# Schematic_v1_1_1.net
KiCad netlist of a schematic drawn in EasyEDA
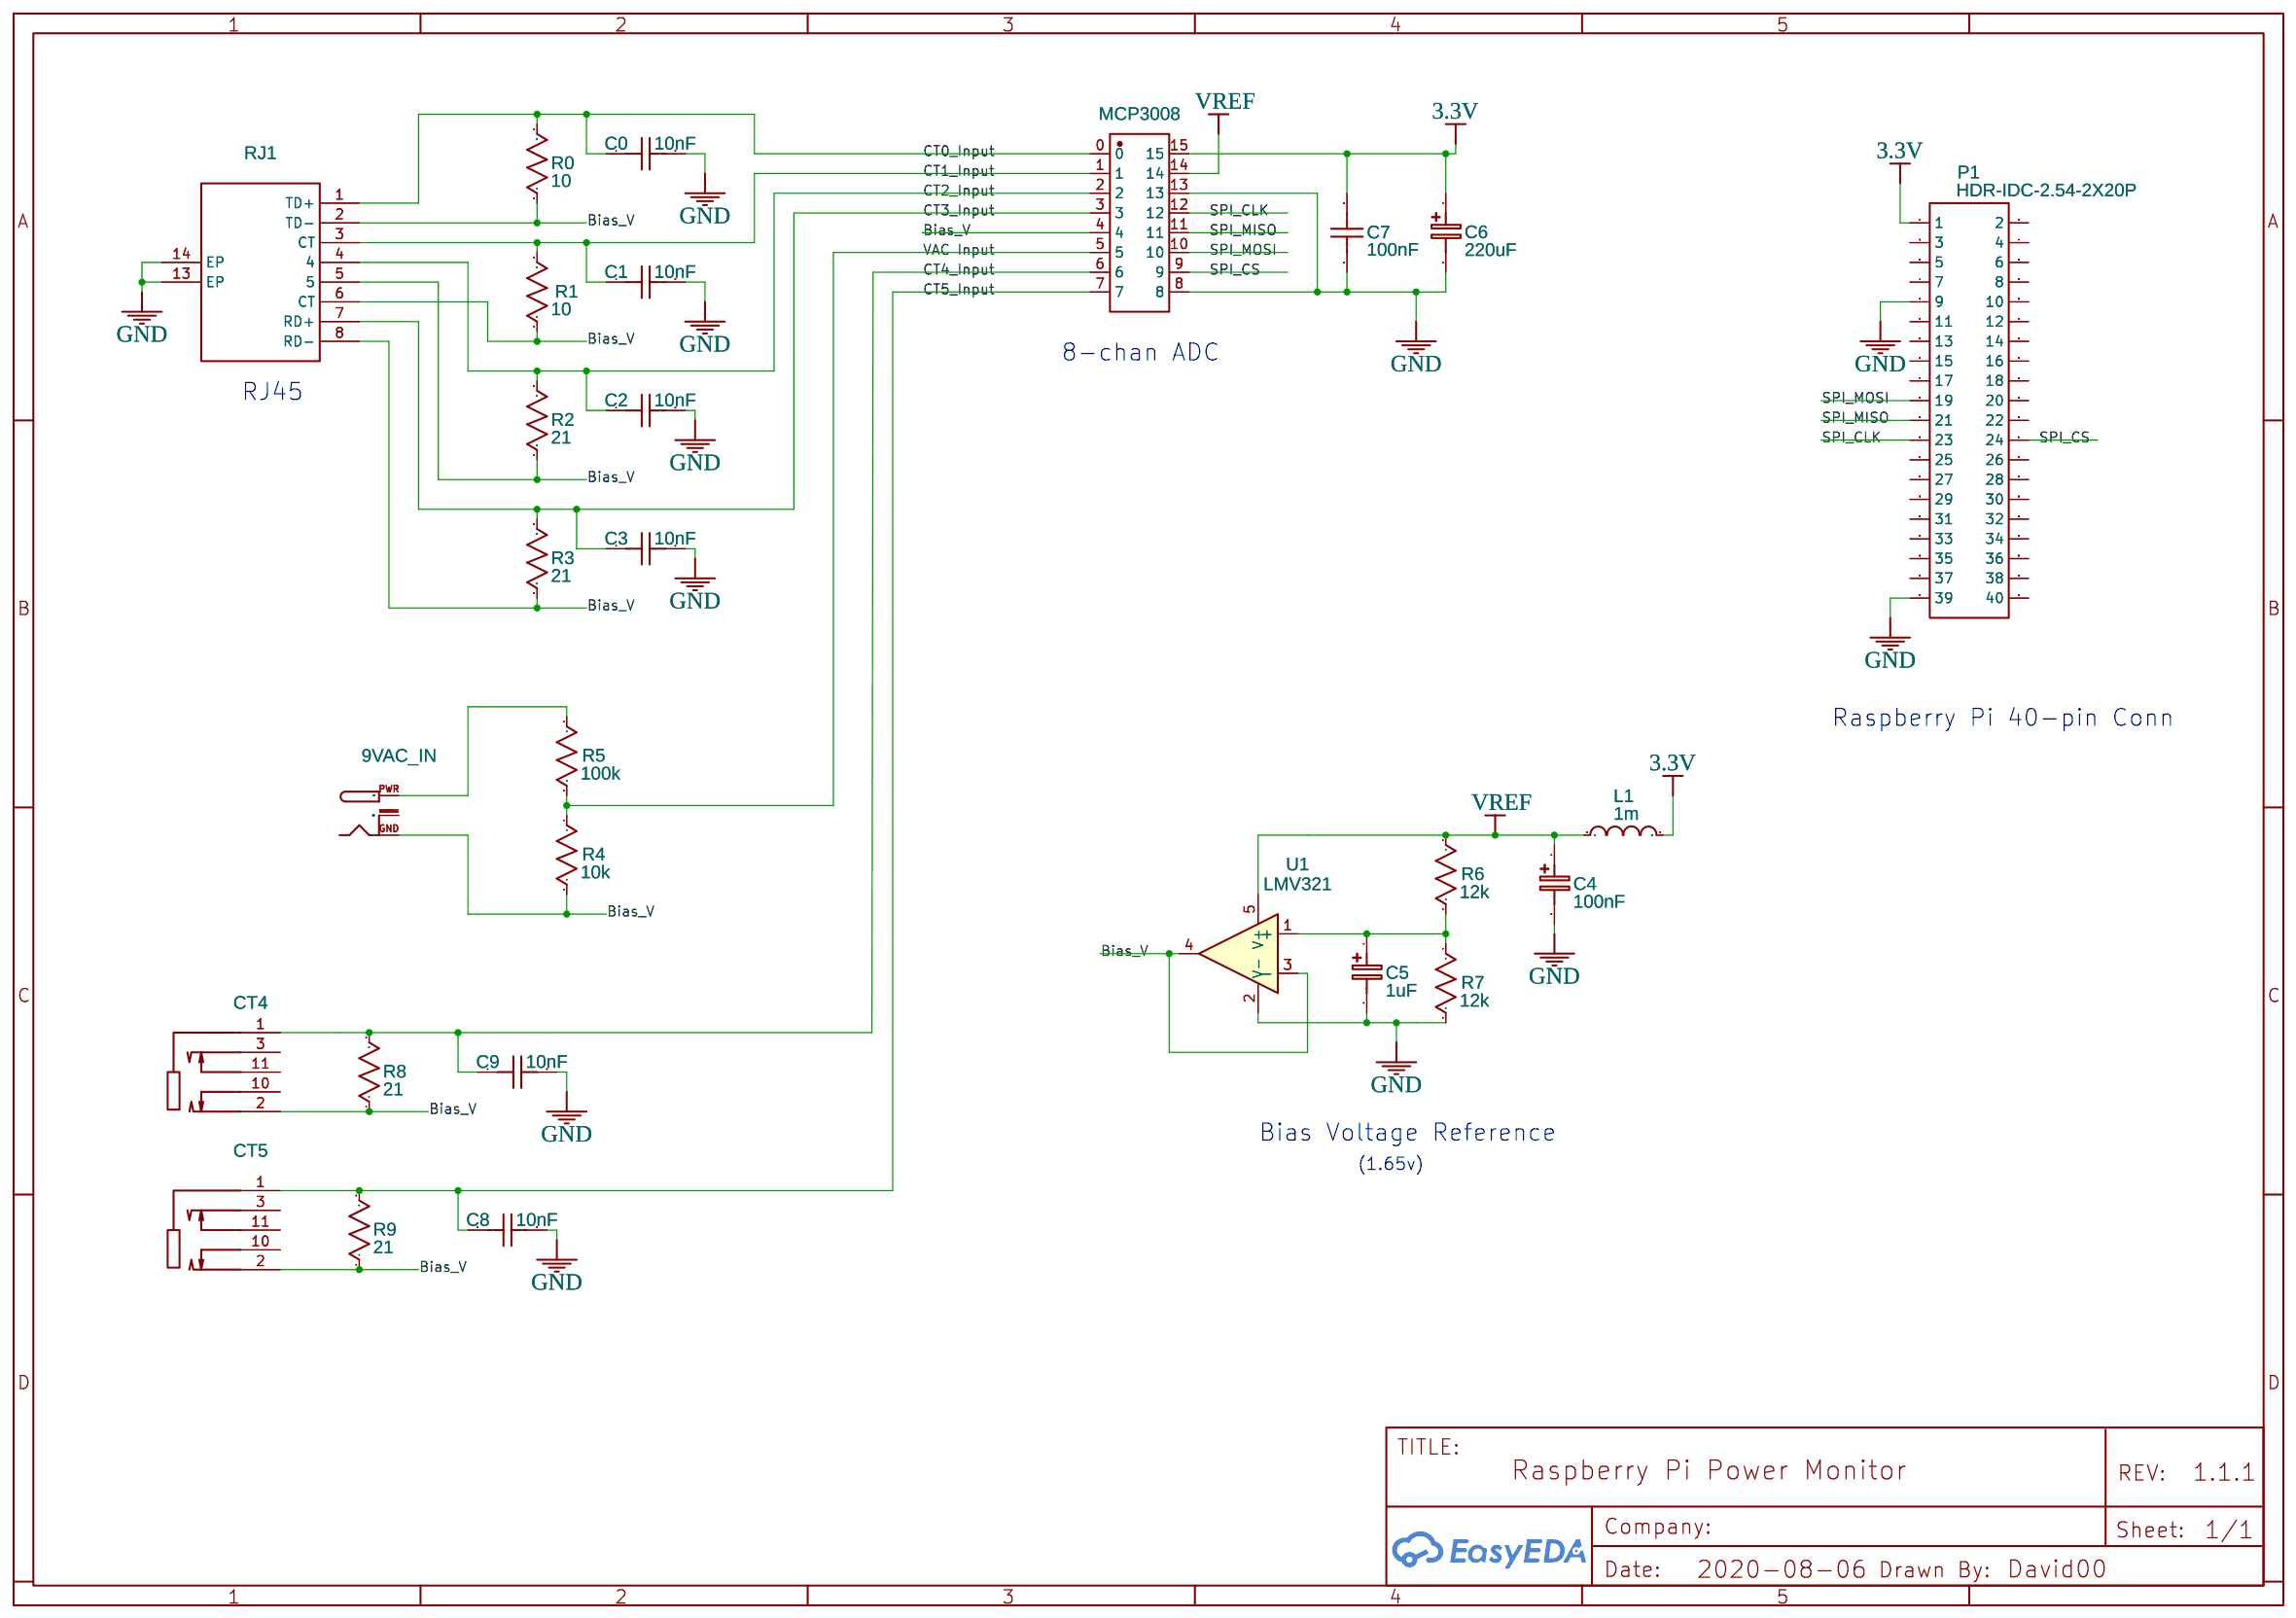
[diagram p0: schematic sheet]

(export (version "E")
  (design (tool "Eeschema 10.0.6"))
  (components
    (comp (ref "9VAC_IN") (value "DCBARRELPTH") (libsource (lib "") (part "DCBARRELPTH")))
    (comp (ref "C0")
      (value "10nF")
      (fields
        (field (name "BOM_Manufacturer Part") "PE103J2A0501")
        (field (name "BOM_Supplier Part") "C390168")
      )
      (libsource (lib "") (part "PE103J2A0501"))
    )
    (comp (ref "C1")
      (value "10nF")
      (fields
        (field (name "BOM_Manufacturer Part") "PE103J2A0501")
        (field (name "BOM_Supplier Part") "C390168")
      )
      (libsource (lib "") (part "PE103J2A0501"))
    )
    (comp (ref "C2")
      (value "10nF")
      (fields
        (field (name "BOM_Manufacturer Part") "PE103J2A0501")
        (field (name "BOM_Supplier Part") "C390168")
      )
      (libsource (lib "") (part "PE103J2A0501"))
    )
    (comp (ref "C3")
      (value "10nF")
      (fields
        (field (name "BOM_Manufacturer Part") "PE103J2A0501")
        (field (name "BOM_Supplier Part") "C390168")
      )
      (libsource (lib "") (part "PE103J2A0501"))
    )
    (comp (ref "C4") (value "100nF") (libsource (lib "") (part "Cap_Electrolytic(TH)_D3.0XF1.5_EU_1")))
    (comp (ref "C5") (value "1uF") (libsource (lib "") (part "Cap_Electrolytic(TH)_D3.0XF1.5_EU_1")))
    (comp (ref "C6") (value "220uF") (libsource (lib "") (part "Cap_Electrolytic(TH)_D3.0XF1.5_EU")))
    (comp (ref "C7")
      (value "100nF")
      (fields
        (field (name "BOM_Manufacturer Part") "CC45SL3AD101JYVNA")
        (field (name "BOM_Supplier Part") "C342396")
      )
      (libsource (lib "") (part "CC45SL3AD101JYVNA"))
    )
    (comp (ref "C8")
      (value "10nF")
      (fields
        (field (name "BOM_Manufacturer Part") "PE103J2A0501")
        (field (name "BOM_Supplier Part") "C390168")
      )
      (libsource (lib "") (part "PE103J2A0501_1"))
    )
    (comp (ref "C9")
      (value "10nF")
      (fields
        (field (name "BOM_Manufacturer Part") "PE103J2A0501")
        (field (name "BOM_Supplier Part") "C390168")
      )
      (libsource (lib "") (part "PE103J2A0501"))
    )
    (comp (ref "CT4")
      (value "PJ-328A0-B")
      (fields (field (name "BOM_Supplier Part") "C381129"))
      (libsource (lib "") (part "PJ-328A0-B"))
    )
    (comp (ref "CT5")
      (value "PJ-328A0-B")
      (fields (field (name "BOM_Supplier Part") "C381129"))
      (libsource (lib "") (part "PJ-328A0-B"))
    )
    (comp (ref "L1") (value "1m") (libsource (lib "") (part "Inductor_AXIAL-0.4_US")))
    (comp (ref "MCP3008")
      (value "IC seat 16P")
      (fields (field (name "BOM_Supplier Part") "C2326"))
      (libsource (lib "") (part "IC seat 16P"))
    )
    (comp (ref "P1")
      (value "HDR-IDC-2.54-2X20P")
      (fields
        (field (name "BOM_Manufacturer Part") "IDC Box 2X20 2.54MM")
        (field (name "BOM_Supplier Part") "C9138")
      )
      (libsource (lib "") (part "HDR-IDC-2.54-2X20P"))
    )
    (comp (ref "R0") (value "10") (libsource (lib "") (part "Res_AXIAL-0.3(1/8W)_US_1")))
    (comp (ref "R1") (value "10") (libsource (lib "") (part "Res_AXIAL-0.3(1/8W)_US_1")))
    (comp (ref "R2") (value "21") (libsource (lib "") (part "Res_AXIAL-0.3(1/8W)_US_1")))
    (comp (ref "R3") (value "21") (libsource (lib "") (part "Res_AXIAL-0.3(1/8W)_US_1")))
    (comp (ref "R4") (value "10k") (libsource (lib "") (part "Res_AXIAL-0.3(1/8W)_US")))
    (comp (ref "R5") (value "100k") (libsource (lib "") (part "Res_AXIAL-0.3(1/8W)_US")))
    (comp (ref "R6") (value "12k") (libsource (lib "") (part "Res_AXIAL-0.3(1/8W)_US")))
    (comp (ref "R7") (value "12k") (libsource (lib "") (part "Res_AXIAL-0.3(1/8W)_US")))
    (comp (ref "R8") (value "21") (libsource (lib "") (part "Res_AXIAL-0.3(1/8W)_US_1")))
    (comp (ref "R9") (value "21") (libsource (lib "") (part "Res_AXIAL-0.3(1/8W)_US_1")))
    (comp (ref "RJ1")
      (value "13F-62ANWA2NL")
      (fields (field (name "BOM_Supplier Part") "C179761"))
      (libsource (lib "") (part "13F-62ANWA2NL"))
    )
    (comp (ref "U1") (value "LMV321") (libsource (lib "") (part "LMV321")))
  )
  (nets
    (net (code "1") (name "/Bias_V") (class "Default")
      (node (ref "9VAC_IN") (pin "GND") (pinfunction "GND_GND") (pintype "passive"))
      (node (ref "CT4") (pin "2") (pinfunction "2_2") (pintype "unspecified"))
      (node (ref "CT5") (pin "2") (pinfunction "2_2") (pintype "unspecified"))
      (node (ref "MCP3008") (pin "4") (pinfunction "4_4") (pintype "unspecified"))
      (node (ref "R0") (pin "1") (pinfunction "1_1") (pintype "unspecified"))
      (node (ref "R1") (pin "1") (pinfunction "1_1") (pintype "unspecified"))
      (node (ref "R2") (pin "1") (pinfunction "1_1") (pintype "unspecified"))
      (node (ref "R3") (pin "1") (pinfunction "1_1") (pintype "unspecified"))
      (node (ref "R4") (pin "2") (pinfunction "2_2") (pintype "unspecified"))
      (node (ref "R8") (pin "1") (pinfunction "1_1") (pintype "unspecified"))
      (node (ref "R9") (pin "1") (pinfunction "1_1") (pintype "unspecified"))
      (node (ref "RJ1") (pin "2") (pinfunction "TD-_2") (pintype "unspecified"))
      (node (ref "RJ1") (pin "5") (pinfunction "5_5") (pintype "unspecified"))
      (node (ref "RJ1") (pin "6") (pinfunction "CT_6") (pintype "unspecified"))
      (node (ref "RJ1") (pin "8") (pinfunction "RD-_8") (pintype "unspecified"))
      (node (ref "U1") (pin "3") (pinfunction "-_3") (pintype "input"))
      (node (ref "U1") (pin "4") (pintype "output"))
    )
    (net (code "2") (name "/CT0_Input") (class "Default")
      (node (ref "C0") (pin "1") (pinfunction "1_1") (pintype "unspecified"))
      (node (ref "MCP3008") (pin "0") (pinfunction "0_0") (pintype "unspecified"))
      (node (ref "R0") (pin "2") (pinfunction "2_2") (pintype "unspecified"))
      (node (ref "RJ1") (pin "1") (pinfunction "TD+_1") (pintype "unspecified"))
    )
    (net (code "3") (name "/CT1_Input") (class "Default")
      (node (ref "C1") (pin "1") (pinfunction "1_1") (pintype "unspecified"))
      (node (ref "MCP3008") (pin "1") (pinfunction "1_1") (pintype "unspecified"))
      (node (ref "R1") (pin "2") (pinfunction "2_2") (pintype "unspecified"))
      (node (ref "RJ1") (pin "3") (pinfunction "CT_3") (pintype "unspecified"))
    )
    (net (code "4") (name "/CT2_Input") (class "Default")
      (node (ref "C2") (pin "1") (pinfunction "1_1") (pintype "unspecified"))
      (node (ref "MCP3008") (pin "2") (pinfunction "2_2") (pintype "unspecified"))
      (node (ref "R2") (pin "2") (pinfunction "2_2") (pintype "unspecified"))
      (node (ref "RJ1") (pin "4") (pinfunction "4_4") (pintype "unspecified"))
    )
    (net (code "5") (name "/CT3_Input") (class "Default")
      (node (ref "C3") (pin "1") (pinfunction "1_1") (pintype "unspecified"))
      (node (ref "MCP3008") (pin "3") (pinfunction "3_3") (pintype "unspecified"))
      (node (ref "R3") (pin "2") (pinfunction "2_2") (pintype "unspecified"))
      (node (ref "RJ1") (pin "7") (pinfunction "RD+_7") (pintype "unspecified"))
    )
    (net (code "6") (name "/CT4_Input") (class "Default")
      (node (ref "C9") (pin "1") (pinfunction "1_1") (pintype "unspecified"))
      (node (ref "CT4") (pin "1") (pinfunction "1_1") (pintype "unspecified"))
      (node (ref "MCP3008") (pin "6") (pinfunction "6_6") (pintype "unspecified"))
      (node (ref "R8") (pin "2") (pinfunction "2_2") (pintype "unspecified"))
    )
    (net (code "7") (name "/CT5_Input") (class "Default")
      (node (ref "C8") (pin "2") (pinfunction "2_2") (pintype "unspecified"))
      (node (ref "CT5") (pin "1") (pinfunction "1_1") (pintype "unspecified"))
      (node (ref "MCP3008") (pin "7") (pinfunction "7_7") (pintype "unspecified"))
      (node (ref "R9") (pin "2") (pinfunction "2_2") (pintype "unspecified"))
    )
    (net (code "8") (name "/SPI_CLK") (class "Default")
      (node (ref "MCP3008") (pin "12") (pinfunction "12_12") (pintype "unspecified"))
      (node (ref "P1") (pin "23") (pinfunction "23_23") (pintype "unspecified"))
    )
    (net (code "9") (name "/SPI_CS") (class "Default")
      (node (ref "MCP3008") (pin "9") (pinfunction "9_9") (pintype "unspecified"))
      (node (ref "P1") (pin "24") (pinfunction "24_24") (pintype "unspecified"))
    )
    (net (code "10") (name "/SPI_MISO") (class "Default")
      (node (ref "MCP3008") (pin "11") (pinfunction "11_11") (pintype "unspecified"))
      (node (ref "P1") (pin "21") (pinfunction "21_21") (pintype "unspecified"))
    )
    (net (code "11") (name "/SPI_MOSI") (class "Default")
      (node (ref "MCP3008") (pin "10") (pinfunction "10_10") (pintype "unspecified"))
      (node (ref "P1") (pin "19") (pinfunction "19_19") (pintype "unspecified"))
    )
    (net (code "12") (name "/VAC Input") (class "Default")
      (node (ref "MCP3008") (pin "5") (pinfunction "5_5") (pintype "unspecified"))
      (node (ref "R4") (pin "1") (pinfunction "1_1") (pintype "unspecified"))
      (node (ref "R5") (pin "2") (pinfunction "2_2") (pintype "unspecified"))
    )
    (net (code "13") (name "3.3V") (class "Default")
      (node (ref "C6") (pin "1") (pinfunction "1_1") (pintype "unspecified"))
      (node (ref "C7") (pin "2") (pinfunction "2_2") (pintype "unspecified"))
      (node (ref "L1") (pin "2") (pinfunction "2_2") (pintype "unspecified"))
      (node (ref "MCP3008") (pin "15") (pinfunction "15_15") (pintype "unspecified"))
      (node (ref "P1") (pin "1") (pinfunction "1_1") (pintype "unspecified"))
    )
    (net (code "14") (name "GND") (class "Default")
      (node (ref "C0") (pin "2") (pinfunction "2_2") (pintype "unspecified"))
      (node (ref "C1") (pin "2") (pinfunction "2_2") (pintype "unspecified"))
      (node (ref "C2") (pin "2") (pinfunction "2_2") (pintype "unspecified"))
      (node (ref "C3") (pin "2") (pinfunction "2_2") (pintype "unspecified"))
      (node (ref "C4") (pin "2") (pinfunction "2_2") (pintype "unspecified"))
      (node (ref "C5") (pin "2") (pinfunction "2_2") (pintype "unspecified"))
      (node (ref "C6") (pin "2") (pinfunction "2_2") (pintype "unspecified"))
      (node (ref "C7") (pin "1") (pinfunction "1_1") (pintype "unspecified"))
      (node (ref "C8") (pin "1") (pinfunction "1_1") (pintype "unspecified"))
      (node (ref "C9") (pin "2") (pinfunction "2_2") (pintype "unspecified"))
      (node (ref "MCP3008") (pin "13") (pinfunction "13_13") (pintype "unspecified"))
      (node (ref "MCP3008") (pin "8") (pinfunction "8_8") (pintype "unspecified"))
      (node (ref "P1") (pin "39") (pinfunction "39_39") (pintype "unspecified"))
      (node (ref "P1") (pin "9") (pinfunction "9_9") (pintype "unspecified"))
      (node (ref "R7") (pin "2") (pinfunction "2_2") (pintype "unspecified"))
      (node (ref "RJ1") (pin "13") (pinfunction "EP_13") (pintype "unspecified"))
      (node (ref "RJ1") (pin "14") (pinfunction "EP_14") (pintype "unspecified"))
      (node (ref "U1") (pin "2") (pinfunction "V-_2") (pintype "bidirectional"))
    )
    (net (code "15") (name "Net-(9VAC_IN-PadPWR)") (class "Default")
      (node (ref "9VAC_IN") (pin "PWR") (pinfunction "PWR_PWR") (pintype "passive"))
      (node (ref "R5") (pin "1") (pinfunction "1_1") (pintype "unspecified"))
    )
    (net (code "16") (name "Net-(U1-+)") (class "Default")
      (node (ref "C5") (pin "1") (pinfunction "1_1") (pintype "unspecified"))
      (node (ref "R6") (pin "2") (pinfunction "2_2") (pintype "unspecified"))
      (node (ref "R7") (pin "1") (pinfunction "1_1") (pintype "unspecified"))
      (node (ref "U1") (pin "1") (pinfunction "+_1") (pintype "input"))
    )
    (net (code "17") (name "VREF") (class "Default")
      (node (ref "C4") (pin "1") (pinfunction "1_1") (pintype "unspecified"))
      (node (ref "L1") (pin "1") (pinfunction "1_1") (pintype "unspecified"))
      (node (ref "MCP3008") (pin "14") (pinfunction "14_14") (pintype "unspecified"))
      (node (ref "R6") (pin "1") (pinfunction "1_1") (pintype "unspecified"))
      (node (ref "U1") (pin "5") (pinfunction "V+_5") (pintype "bidirectional"))
    )
    (net (code "18") (name "unconnected-(9VAC_IN-PadGNDBREAK)") (class "Default")
      (node (ref "9VAC_IN") (pin "GNDBREAK") (pinfunction "GNDBREAK_GNDBREAK") (pintype "passive"))
    )
    (net (code "19") (name "unconnected-(CT4-Pad3)") (class "Default")
      (node (ref "CT4") (pin "3") (pinfunction "3_3") (pintype "unspecified"))
    )
    (net (code "20") (name "unconnected-(CT4-Pad10)") (class "Default")
      (node (ref "CT4") (pin "10") (pinfunction "10_10") (pintype "unspecified"))
    )
    (net (code "21") (name "unconnected-(CT4-Pad11)") (class "Default")
      (node (ref "CT4") (pin "11") (pinfunction "11_11") (pintype "unspecified"))
    )
    (net (code "22") (name "unconnected-(CT5-Pad3)") (class "Default")
      (node (ref "CT5") (pin "3") (pinfunction "3_3") (pintype "unspecified"))
    )
    (net (code "23") (name "unconnected-(CT5-Pad10)") (class "Default")
      (node (ref "CT5") (pin "10") (pinfunction "10_10") (pintype "unspecified"))
    )
    (net (code "24") (name "unconnected-(CT5-Pad11)") (class "Default")
      (node (ref "CT5") (pin "11") (pinfunction "11_11") (pintype "unspecified"))
    )
    (net (code "25") (name "unconnected-(P1-Pad2)") (class "Default")
      (node (ref "P1") (pin "2") (pinfunction "2_2") (pintype "unspecified"))
    )
    (net (code "26") (name "unconnected-(P1-Pad3)") (class "Default")
      (node (ref "P1") (pin "3") (pinfunction "3_3") (pintype "unspecified"))
    )
    (net (code "27") (name "unconnected-(P1-Pad4)") (class "Default")
      (node (ref "P1") (pin "4") (pinfunction "4_4") (pintype "unspecified"))
    )
    (net (code "28") (name "unconnected-(P1-Pad5)") (class "Default")
      (node (ref "P1") (pin "5") (pinfunction "5_5") (pintype "unspecified"))
    )
    (net (code "29") (name "unconnected-(P1-Pad6)") (class "Default")
      (node (ref "P1") (pin "6") (pinfunction "6_6") (pintype "unspecified"))
    )
    (net (code "30") (name "unconnected-(P1-Pad7)") (class "Default")
      (node (ref "P1") (pin "7") (pinfunction "7_7") (pintype "unspecified"))
    )
    (net (code "31") (name "unconnected-(P1-Pad8)") (class "Default")
      (node (ref "P1") (pin "8") (pinfunction "8_8") (pintype "unspecified"))
    )
    (net (code "32") (name "unconnected-(P1-Pad10)") (class "Default")
      (node (ref "P1") (pin "10") (pinfunction "10_10") (pintype "unspecified"))
    )
    (net (code "33") (name "unconnected-(P1-Pad11)") (class "Default")
      (node (ref "P1") (pin "11") (pinfunction "11_11") (pintype "unspecified"))
    )
    (net (code "34") (name "unconnected-(P1-Pad12)") (class "Default")
      (node (ref "P1") (pin "12") (pinfunction "12_12") (pintype "unspecified"))
    )
    (net (code "35") (name "unconnected-(P1-Pad13)") (class "Default")
      (node (ref "P1") (pin "13") (pinfunction "13_13") (pintype "unspecified"))
    )
    (net (code "36") (name "unconnected-(P1-Pad14)") (class "Default")
      (node (ref "P1") (pin "14") (pinfunction "14_14") (pintype "unspecified"))
    )
    (net (code "37") (name "unconnected-(P1-Pad15)") (class "Default")
      (node (ref "P1") (pin "15") (pinfunction "15_15") (pintype "unspecified"))
    )
    (net (code "38") (name "unconnected-(P1-Pad16)") (class "Default")
      (node (ref "P1") (pin "16") (pinfunction "16_16") (pintype "unspecified"))
    )
    (net (code "39") (name "unconnected-(P1-Pad17)") (class "Default")
      (node (ref "P1") (pin "17") (pinfunction "17_17") (pintype "unspecified"))
    )
    (net (code "40") (name "unconnected-(P1-Pad18)") (class "Default")
      (node (ref "P1") (pin "18") (pinfunction "18_18") (pintype "unspecified"))
    )
    (net (code "41") (name "unconnected-(P1-Pad20)") (class "Default")
      (node (ref "P1") (pin "20") (pinfunction "20_20") (pintype "unspecified"))
    )
    (net (code "42") (name "unconnected-(P1-Pad22)") (class "Default")
      (node (ref "P1") (pin "22") (pinfunction "22_22") (pintype "unspecified"))
    )
    (net (code "43") (name "unconnected-(P1-Pad25)") (class "Default")
      (node (ref "P1") (pin "25") (pinfunction "25_25") (pintype "unspecified"))
    )
    (net (code "44") (name "unconnected-(P1-Pad26)") (class "Default")
      (node (ref "P1") (pin "26") (pinfunction "26_26") (pintype "unspecified"))
    )
    (net (code "45") (name "unconnected-(P1-Pad27)") (class "Default")
      (node (ref "P1") (pin "27") (pinfunction "27_27") (pintype "unspecified"))
    )
    (net (code "46") (name "unconnected-(P1-Pad28)") (class "Default")
      (node (ref "P1") (pin "28") (pinfunction "28_28") (pintype "unspecified"))
    )
    (net (code "47") (name "unconnected-(P1-Pad29)") (class "Default")
      (node (ref "P1") (pin "29") (pinfunction "29_29") (pintype "unspecified"))
    )
    (net (code "48") (name "unconnected-(P1-Pad30)") (class "Default")
      (node (ref "P1") (pin "30") (pinfunction "30_30") (pintype "unspecified"))
    )
    (net (code "49") (name "unconnected-(P1-Pad31)") (class "Default")
      (node (ref "P1") (pin "31") (pinfunction "31_31") (pintype "unspecified"))
    )
    (net (code "50") (name "unconnected-(P1-Pad32)") (class "Default")
      (node (ref "P1") (pin "32") (pinfunction "32_32") (pintype "unspecified"))
    )
    (net (code "51") (name "unconnected-(P1-Pad33)") (class "Default")
      (node (ref "P1") (pin "33") (pinfunction "33_33") (pintype "unspecified"))
    )
    (net (code "52") (name "unconnected-(P1-Pad34)") (class "Default")
      (node (ref "P1") (pin "34") (pinfunction "34_34") (pintype "unspecified"))
    )
    (net (code "53") (name "unconnected-(P1-Pad35)") (class "Default")
      (node (ref "P1") (pin "35") (pinfunction "35_35") (pintype "unspecified"))
    )
    (net (code "54") (name "unconnected-(P1-Pad36)") (class "Default")
      (node (ref "P1") (pin "36") (pinfunction "36_36") (pintype "unspecified"))
    )
    (net (code "55") (name "unconnected-(P1-Pad37)") (class "Default")
      (node (ref "P1") (pin "37") (pinfunction "37_37") (pintype "unspecified"))
    )
    (net (code "56") (name "unconnected-(P1-Pad38)") (class "Default")
      (node (ref "P1") (pin "38") (pinfunction "38_38") (pintype "unspecified"))
    )
    (net (code "57") (name "unconnected-(P1-Pad40)") (class "Default")
      (node (ref "P1") (pin "40") (pinfunction "40_40") (pintype "unspecified"))
    )
  )
)
